# OpenLabKostkaSchematPomiarowy3.net
KiCad netlist of a schematic drawn in EAGLE
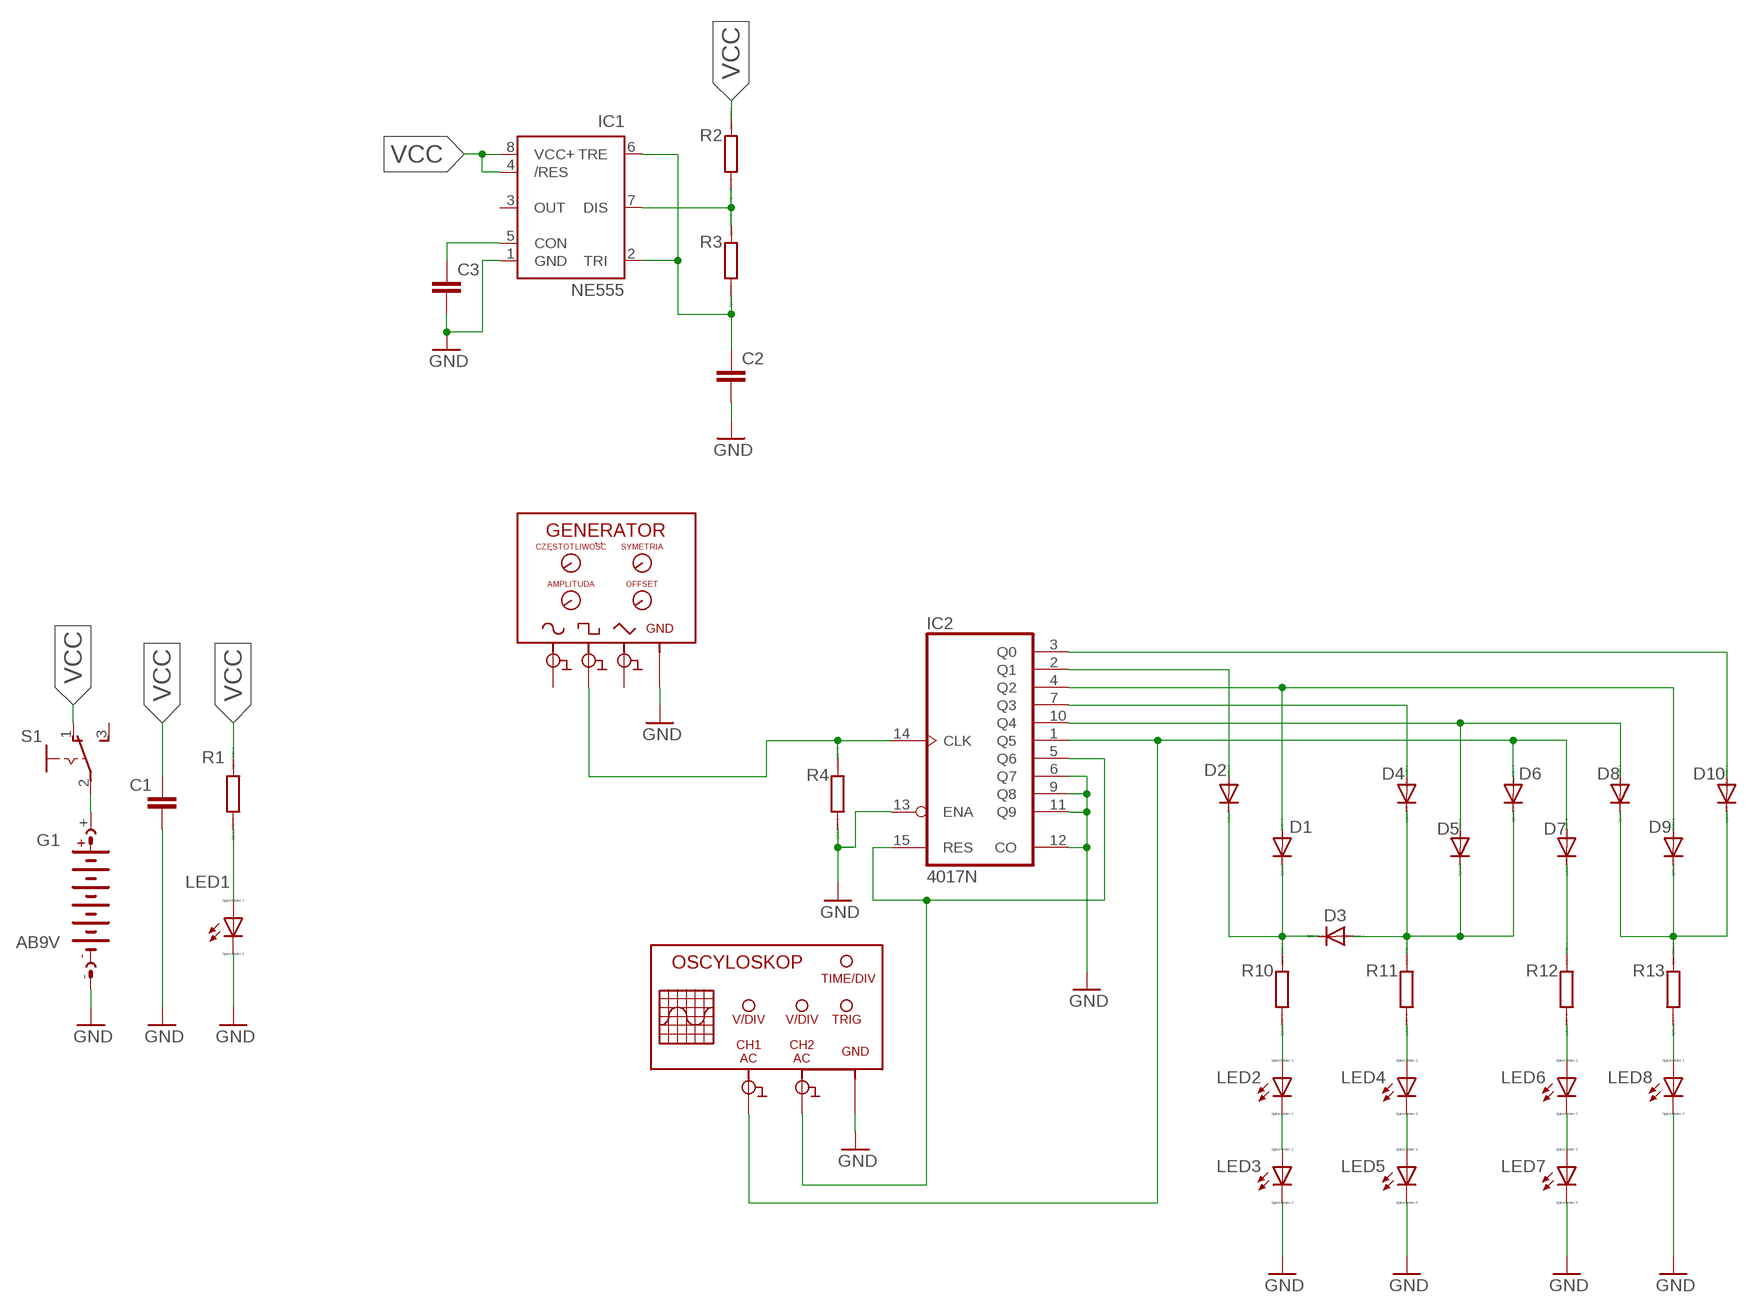
[diagram p0: schematic, sheet 1]

(export (version "E")
  (design (tool "Eeschema 10.0.6"))
  (components
    (comp (ref "C1")
      (value "C5/2.5")
      (footprint "eagle-import:C5B2.5")
      (libsource (lib "eagle-import") (part "C5/2.5"))
    )
    (comp (ref "C2")
      (value "C5/2.5")
      (footprint "eagle-import:C5B2.5")
      (libsource (lib "eagle-import") (part "C5/2.5"))
    )
    (comp (ref "C3")
      (value "C5/2.5")
      (footprint "eagle-import:C5B2.5")
      (libsource (lib "eagle-import") (part "C5/2.5"))
    )
    (comp (ref "D1")
      (value "1N4446")
      (footprint "eagle-import:DO35-10")
      (libsource (lib "eagle-import") (part "1N4446"))
    )
    (comp (ref "D2")
      (value "1N4446")
      (footprint "eagle-import:DO35-10")
      (libsource (lib "eagle-import") (part "1N4446"))
    )
    (comp (ref "D3")
      (value "1N4446")
      (footprint "eagle-import:DO35-10")
      (libsource (lib "eagle-import") (part "1N4446"))
    )
    (comp (ref "D4")
      (value "1N4446")
      (footprint "eagle-import:DO35-10")
      (libsource (lib "eagle-import") (part "1N4446"))
    )
    (comp (ref "D5")
      (value "1N4446")
      (footprint "eagle-import:DO35-10")
      (libsource (lib "eagle-import") (part "1N4446"))
    )
    (comp (ref "D6")
      (value "1N4446")
      (footprint "eagle-import:DO35-10")
      (libsource (lib "eagle-import") (part "1N4446"))
    )
    (comp (ref "D7")
      (value "1N4446")
      (footprint "eagle-import:DO35-10")
      (libsource (lib "eagle-import") (part "1N4446"))
    )
    (comp (ref "D8")
      (value "1N4446")
      (footprint "eagle-import:DO35-10")
      (libsource (lib "eagle-import") (part "1N4446"))
    )
    (comp (ref "D9")
      (value "1N4446")
      (footprint "eagle-import:DO35-10")
      (libsource (lib "eagle-import") (part "1N4446"))
    )
    (comp (ref "D10")
      (value "1N4446")
      (footprint "eagle-import:DO35-10")
      (libsource (lib "eagle-import") (part "1N4446"))
    )
    (comp (ref "G1")
      (value "AB9V")
      (footprint "eagle-import:AB9V")
      (libsource (lib "eagle-import") (part "AB9V"))
    )
    (comp (ref "IC1")
      (value "NE555")
      (footprint "eagle-import:DIL-08")
      (fields (field (name "MF") "Arrow Electronics") (field (name "MPN") "NE555N"))
      (libsource (lib "eagle-import") (part "NE555"))
    )
    (comp (ref "IC2")
      (value "4017N")
      (footprint "eagle-import:DIL16")
      (libsource (lib "eagle-import") (part "4017N"))
    )
    (comp (ref "LED1")
      (value "LED_ELD260")
      (footprint "eagle-import:LED_LD260")
      (libsource (lib "eagle-import") (part "LED_ELD260"))
    )
    (comp (ref "LED2")
      (value "LED_ELD260")
      (footprint "eagle-import:LED_LD260")
      (libsource (lib "eagle-import") (part "LED_ELD260"))
    )
    (comp (ref "LED3")
      (value "LED_ELD260")
      (footprint "eagle-import:LED_LD260")
      (libsource (lib "eagle-import") (part "LED_ELD260"))
    )
    (comp (ref "LED4")
      (value "LED_ELD260")
      (footprint "eagle-import:LED_LD260")
      (libsource (lib "eagle-import") (part "LED_ELD260"))
    )
    (comp (ref "LED5")
      (value "LED_ELD260")
      (footprint "eagle-import:LED_LD260")
      (libsource (lib "eagle-import") (part "LED_ELD260"))
    )
    (comp (ref "LED6")
      (value "LED_ELD260")
      (footprint "eagle-import:LED_LD260")
      (libsource (lib "eagle-import") (part "LED_ELD260"))
    )
    (comp (ref "LED7")
      (value "LED_ELD260")
      (footprint "eagle-import:LED_LD260")
      (libsource (lib "eagle-import") (part "LED_ELD260"))
    )
    (comp (ref "LED8")
      (value "LED_ELD260")
      (footprint "eagle-import:LED_LD260")
      (libsource (lib "eagle-import") (part "LED_ELD260"))
    )
    (comp (ref "R1")
      (value "R0204/7")
      (footprint "eagle-import:0204_7")
      (libsource (lib "eagle-import") (part "R0204/7"))
    )
    (comp (ref "R2")
      (value "R0204/7")
      (footprint "eagle-import:0204_7")
      (libsource (lib "eagle-import") (part "R0204/7"))
    )
    (comp (ref "R3")
      (value "R0204/7")
      (footprint "eagle-import:0204_7")
      (libsource (lib "eagle-import") (part "R0204/7"))
    )
    (comp (ref "R4")
      (value "R0204/7")
      (footprint "eagle-import:0204_7")
      (libsource (lib "eagle-import") (part "R0204/7"))
    )
    (comp (ref "R10")
      (value "R0204/7")
      (footprint "eagle-import:0204_7")
      (libsource (lib "eagle-import") (part "R0204/7"))
    )
    (comp (ref "R11")
      (value "R0204/7")
      (footprint "eagle-import:0204_7")
      (libsource (lib "eagle-import") (part "R0204/7"))
    )
    (comp (ref "R12")
      (value "R0204/7")
      (footprint "eagle-import:0204_7")
      (libsource (lib "eagle-import") (part "R0204/7"))
    )
    (comp (ref "R13")
      (value "R0204/7")
      (footprint "eagle-import:0204_7")
      (libsource (lib "eagle-import") (part "R0204/7"))
    )
    (comp (ref "S1")
      (value "255SB")
      (footprint "eagle-import:255SB")
      (libsource (lib "eagle-import") (part "255SB"))
    )
    (comp (ref "U$1")
      (value "OSCYLOSKOP_AC_AC")
      (footprint "eagle-import:OSCYLOSKOP")
      (libsource (lib "eagle-import") (part "OSCYLOSKOP_AC_AC"))
    )
    (comp (ref "U$2")
      (value "GENERATOR")
      (footprint "eagle-import:GENERATOR")
      (libsource (lib "eagle-import") (part "GENERATOR"))
    )
  )
  (nets
    (net (code "1") (name "GND") (class "Default")
      (node (ref "C1") (pin "1") (pinfunction "1_1") (pintype "passive"))
      (node (ref "C2") (pin "2") (pinfunction "2_2") (pintype "passive"))
      (node (ref "C3") (pin "2") (pinfunction "2_2") (pintype "passive"))
      (node (ref "G1") (pin "-") (pinfunction "-_-") (pintype "passive"))
      (node (ref "IC1") (pin "1") (pinfunction "GND_1") (pintype "power_in"))
      (node (ref "IC2") (pin "11") (pinfunction "Q9_11") (pintype "output"))
      (node (ref "IC2") (pin "12") (pinfunction "CO_12") (pintype "output"))
      (node (ref "IC2") (pin "13") (pinfunction "ENA_13") (pintype "input"))
      (node (ref "IC2") (pin "6") (pinfunction "Q7_6") (pintype "output"))
      (node (ref "IC2") (pin "9") (pinfunction "Q8_9") (pintype "output"))
      (node (ref "LED1") (pin "K") (pinfunction "C_K") (pintype "passive"))
      (node (ref "LED3") (pin "K") (pinfunction "C_K") (pintype "passive"))
      (node (ref "LED5") (pin "K") (pinfunction "C_K") (pintype "passive"))
      (node (ref "LED7") (pin "K") (pinfunction "C_K") (pintype "passive"))
      (node (ref "LED8") (pin "K") (pinfunction "C_K") (pintype "passive"))
      (node (ref "R4") (pin "1") (pinfunction "1_1") (pintype "passive"))
      (node (ref "U$1") (pin "GND") (pinfunction "GND_GND") (pintype "bidirectional"))
      (node (ref "U$2") (pin "GND") (pinfunction "GND_GND") (pintype "bidirectional"))
    )
    (net (code "2") (name "Net-(D1-PadC)") (class "Default")
      (node (ref "D1") (pin "C") (pinfunction "C_C") (pintype "passive"))
      (node (ref "D2") (pin "C") (pinfunction "C_C") (pintype "passive"))
      (node (ref "D3") (pin "C") (pinfunction "C_C") (pintype "passive"))
      (node (ref "R10") (pin "2") (pinfunction "2_2") (pintype "passive"))
    )
    (net (code "3") (name "Net-(D3-PadA)") (class "Default")
      (node (ref "D3") (pin "A") (pinfunction "A_A") (pintype "passive"))
      (node (ref "D4") (pin "C") (pinfunction "C_C") (pintype "passive"))
      (node (ref "D5") (pin "C") (pinfunction "C_C") (pintype "passive"))
      (node (ref "D6") (pin "C") (pinfunction "C_C") (pintype "passive"))
      (node (ref "R11") (pin "2") (pinfunction "2_2") (pintype "passive"))
    )
    (net (code "4") (name "Net-(D7-PadC)") (class "Default")
      (node (ref "D7") (pin "C") (pinfunction "C_C") (pintype "passive"))
      (node (ref "R12") (pin "2") (pinfunction "2_2") (pintype "passive"))
    )
    (net (code "5") (name "Net-(D10-PadC)") (class "Default")
      (node (ref "D10") (pin "C") (pinfunction "C_C") (pintype "passive"))
      (node (ref "D8") (pin "C") (pinfunction "C_C") (pintype "passive"))
      (node (ref "D9") (pin "C") (pinfunction "C_C") (pintype "passive"))
      (node (ref "R13") (pin "2") (pinfunction "2_2") (pintype "passive"))
    )
    (net (code "6") (name "Net-(IC1-CON)") (class "Default")
      (node (ref "C3") (pin "1") (pinfunction "1_1") (pintype "passive"))
      (node (ref "IC1") (pin "5") (pinfunction "CON_5") (pintype "input"))
    )
    (net (code "7") (name "Net-(IC1-DIS)") (class "Default")
      (node (ref "IC1") (pin "7") (pinfunction "DIS_7") (pintype "input"))
      (node (ref "R2") (pin "1") (pinfunction "1_1") (pintype "passive"))
      (node (ref "R3") (pin "2") (pinfunction "2_2") (pintype "passive"))
    )
    (net (code "8") (name "Net-(IC1-TRE)") (class "Default")
      (node (ref "C2") (pin "1") (pinfunction "1_1") (pintype "passive"))
      (node (ref "IC1") (pin "2") (pinfunction "TRI_2") (pintype "input"))
      (node (ref "IC1") (pin "6") (pinfunction "TRE_6") (pintype "input"))
      (node (ref "R3") (pin "1") (pinfunction "1_1") (pintype "passive"))
    )
    (net (code "9") (name "Net-(IC2A-CLK)") (class "Default")
      (node (ref "IC2") (pin "14") (pinfunction "CLK_14") (pintype "input"))
      (node (ref "R4") (pin "2") (pinfunction "2_2") (pintype "passive"))
      (node (ref "U$2") (pin "SQ") (pinfunction "SQ_SQ") (pintype "bidirectional"))
    )
    (net (code "10") (name "Net-(IC2A-Q0)") (class "Default")
      (node (ref "D10") (pin "A") (pinfunction "A_A") (pintype "passive"))
      (node (ref "IC2") (pin "3") (pinfunction "Q0_3") (pintype "output"))
    )
    (net (code "11") (name "Net-(IC2A-Q1)") (class "Default")
      (node (ref "D2") (pin "A") (pinfunction "A_A") (pintype "passive"))
      (node (ref "IC2") (pin "2") (pinfunction "Q1_2") (pintype "output"))
    )
    (net (code "12") (name "Net-(IC2A-Q2)") (class "Default")
      (node (ref "D1") (pin "A") (pinfunction "A_A") (pintype "passive"))
      (node (ref "D9") (pin "A") (pinfunction "A_A") (pintype "passive"))
      (node (ref "IC2") (pin "4") (pinfunction "Q2_4") (pintype "output"))
    )
    (net (code "13") (name "Net-(IC2A-Q3)") (class "Default")
      (node (ref "D4") (pin "A") (pinfunction "A_A") (pintype "passive"))
      (node (ref "IC2") (pin "7") (pinfunction "Q3_7") (pintype "output"))
    )
    (net (code "14") (name "Net-(IC2A-Q4)") (class "Default")
      (node (ref "D5") (pin "A") (pinfunction "A_A") (pintype "passive"))
      (node (ref "D8") (pin "A") (pinfunction "A_A") (pintype "passive"))
      (node (ref "IC2") (pin "10") (pinfunction "Q4_10") (pintype "output"))
    )
    (net (code "15") (name "Net-(IC2A-Q5)") (class "Default")
      (node (ref "D6") (pin "A") (pinfunction "A_A") (pintype "passive"))
      (node (ref "D7") (pin "A") (pinfunction "A_A") (pintype "passive"))
      (node (ref "IC2") (pin "1") (pinfunction "Q5_1") (pintype "output"))
      (node (ref "U$1") (pin "CH1") (pinfunction "CH1_CH1") (pintype "bidirectional"))
    )
    (net (code "16") (name "Net-(IC2A-Q6)") (class "Default")
      (node (ref "IC2") (pin "15") (pinfunction "RES_15") (pintype "input"))
      (node (ref "IC2") (pin "5") (pinfunction "Q6_5") (pintype "output"))
      (node (ref "U$1") (pin "CH2") (pinfunction "CH2_CH2") (pintype "bidirectional"))
    )
    (net (code "17") (name "Net-(LED1-PadA)") (class "Default")
      (node (ref "LED1") (pin "A") (pinfunction "A_A") (pintype "passive"))
      (node (ref "R1") (pin "1") (pinfunction "1_1") (pintype "passive"))
    )
    (net (code "18") (name "Net-(LED2-C)") (class "Default")
      (node (ref "LED2") (pin "K") (pinfunction "C_K") (pintype "passive"))
      (node (ref "LED3") (pin "A") (pinfunction "A_A") (pintype "passive"))
    )
    (net (code "19") (name "Net-(LED2-PadA)") (class "Default")
      (node (ref "LED2") (pin "A") (pinfunction "A_A") (pintype "passive"))
      (node (ref "R10") (pin "1") (pinfunction "1_1") (pintype "passive"))
    )
    (net (code "20") (name "Net-(LED4-C)") (class "Default")
      (node (ref "LED4") (pin "K") (pinfunction "C_K") (pintype "passive"))
      (node (ref "LED5") (pin "A") (pinfunction "A_A") (pintype "passive"))
    )
    (net (code "21") (name "Net-(LED4-PadA)") (class "Default")
      (node (ref "LED4") (pin "A") (pinfunction "A_A") (pintype "passive"))
      (node (ref "R11") (pin "1") (pinfunction "1_1") (pintype "passive"))
    )
    (net (code "22") (name "Net-(LED6-C)") (class "Default")
      (node (ref "LED6") (pin "K") (pinfunction "C_K") (pintype "passive"))
      (node (ref "LED7") (pin "A") (pinfunction "A_A") (pintype "passive"))
    )
    (net (code "23") (name "Net-(LED6-PadA)") (class "Default")
      (node (ref "LED6") (pin "A") (pinfunction "A_A") (pintype "passive"))
      (node (ref "R12") (pin "1") (pinfunction "1_1") (pintype "passive"))
    )
    (net (code "24") (name "Net-(LED8-PadA)") (class "Default")
      (node (ref "LED8") (pin "A") (pinfunction "A_A") (pintype "passive"))
      (node (ref "R13") (pin "1") (pinfunction "1_1") (pintype "passive"))
    )
    (net (code "25") (name "Net-(S1-P)") (class "Default")
      (node (ref "G1") (pin "+") (pinfunction "+_+") (pintype "passive"))
      (node (ref "S1") (pin "2") (pinfunction "P_2") (pintype "passive"))
    )
    (net (code "26") (name "VCC") (class "Default")
      (node (ref "C1") (pin "2") (pinfunction "2_2") (pintype "passive"))
      (node (ref "IC1") (pin "4") (pinfunction "/RES_4") (pintype "input"))
      (node (ref "IC1") (pin "8") (pinfunction "VCC+_8") (pintype "power_in"))
      (node (ref "R1") (pin "2") (pinfunction "2_2") (pintype "passive"))
      (node (ref "R2") (pin "2") (pinfunction "2_2") (pintype "passive"))
      (node (ref "S1") (pin "1") (pinfunction "O_1") (pintype "passive"))
    )
    (net (code "27") (name "unconnected-(IC1-OUT-Pad3)") (class "Default")
      (node (ref "IC1") (pin "3") (pinfunction "OUT_3") (pintype "output"))
    )
    (net (code "28") (name "unconnected-(S1-S-Pad3)") (class "Default")
      (node (ref "S1") (pin "3") (pinfunction "S_3") (pintype "passive"))
    )
    (net (code "29") (name "unconnected-(U$2-PadS)") (class "Default")
      (node (ref "U$2") (pin "S") (pinfunction "S_S") (pintype "bidirectional"))
    )
    (net (code "30") (name "unconnected-(U$2-PadTR)") (class "Default")
      (node (ref "U$2") (pin "TR") (pinfunction "TR_TR") (pintype "bidirectional"))
    )
  )
)
